# display.net
KiCad netlist of a schematic drawn in Altium Designer
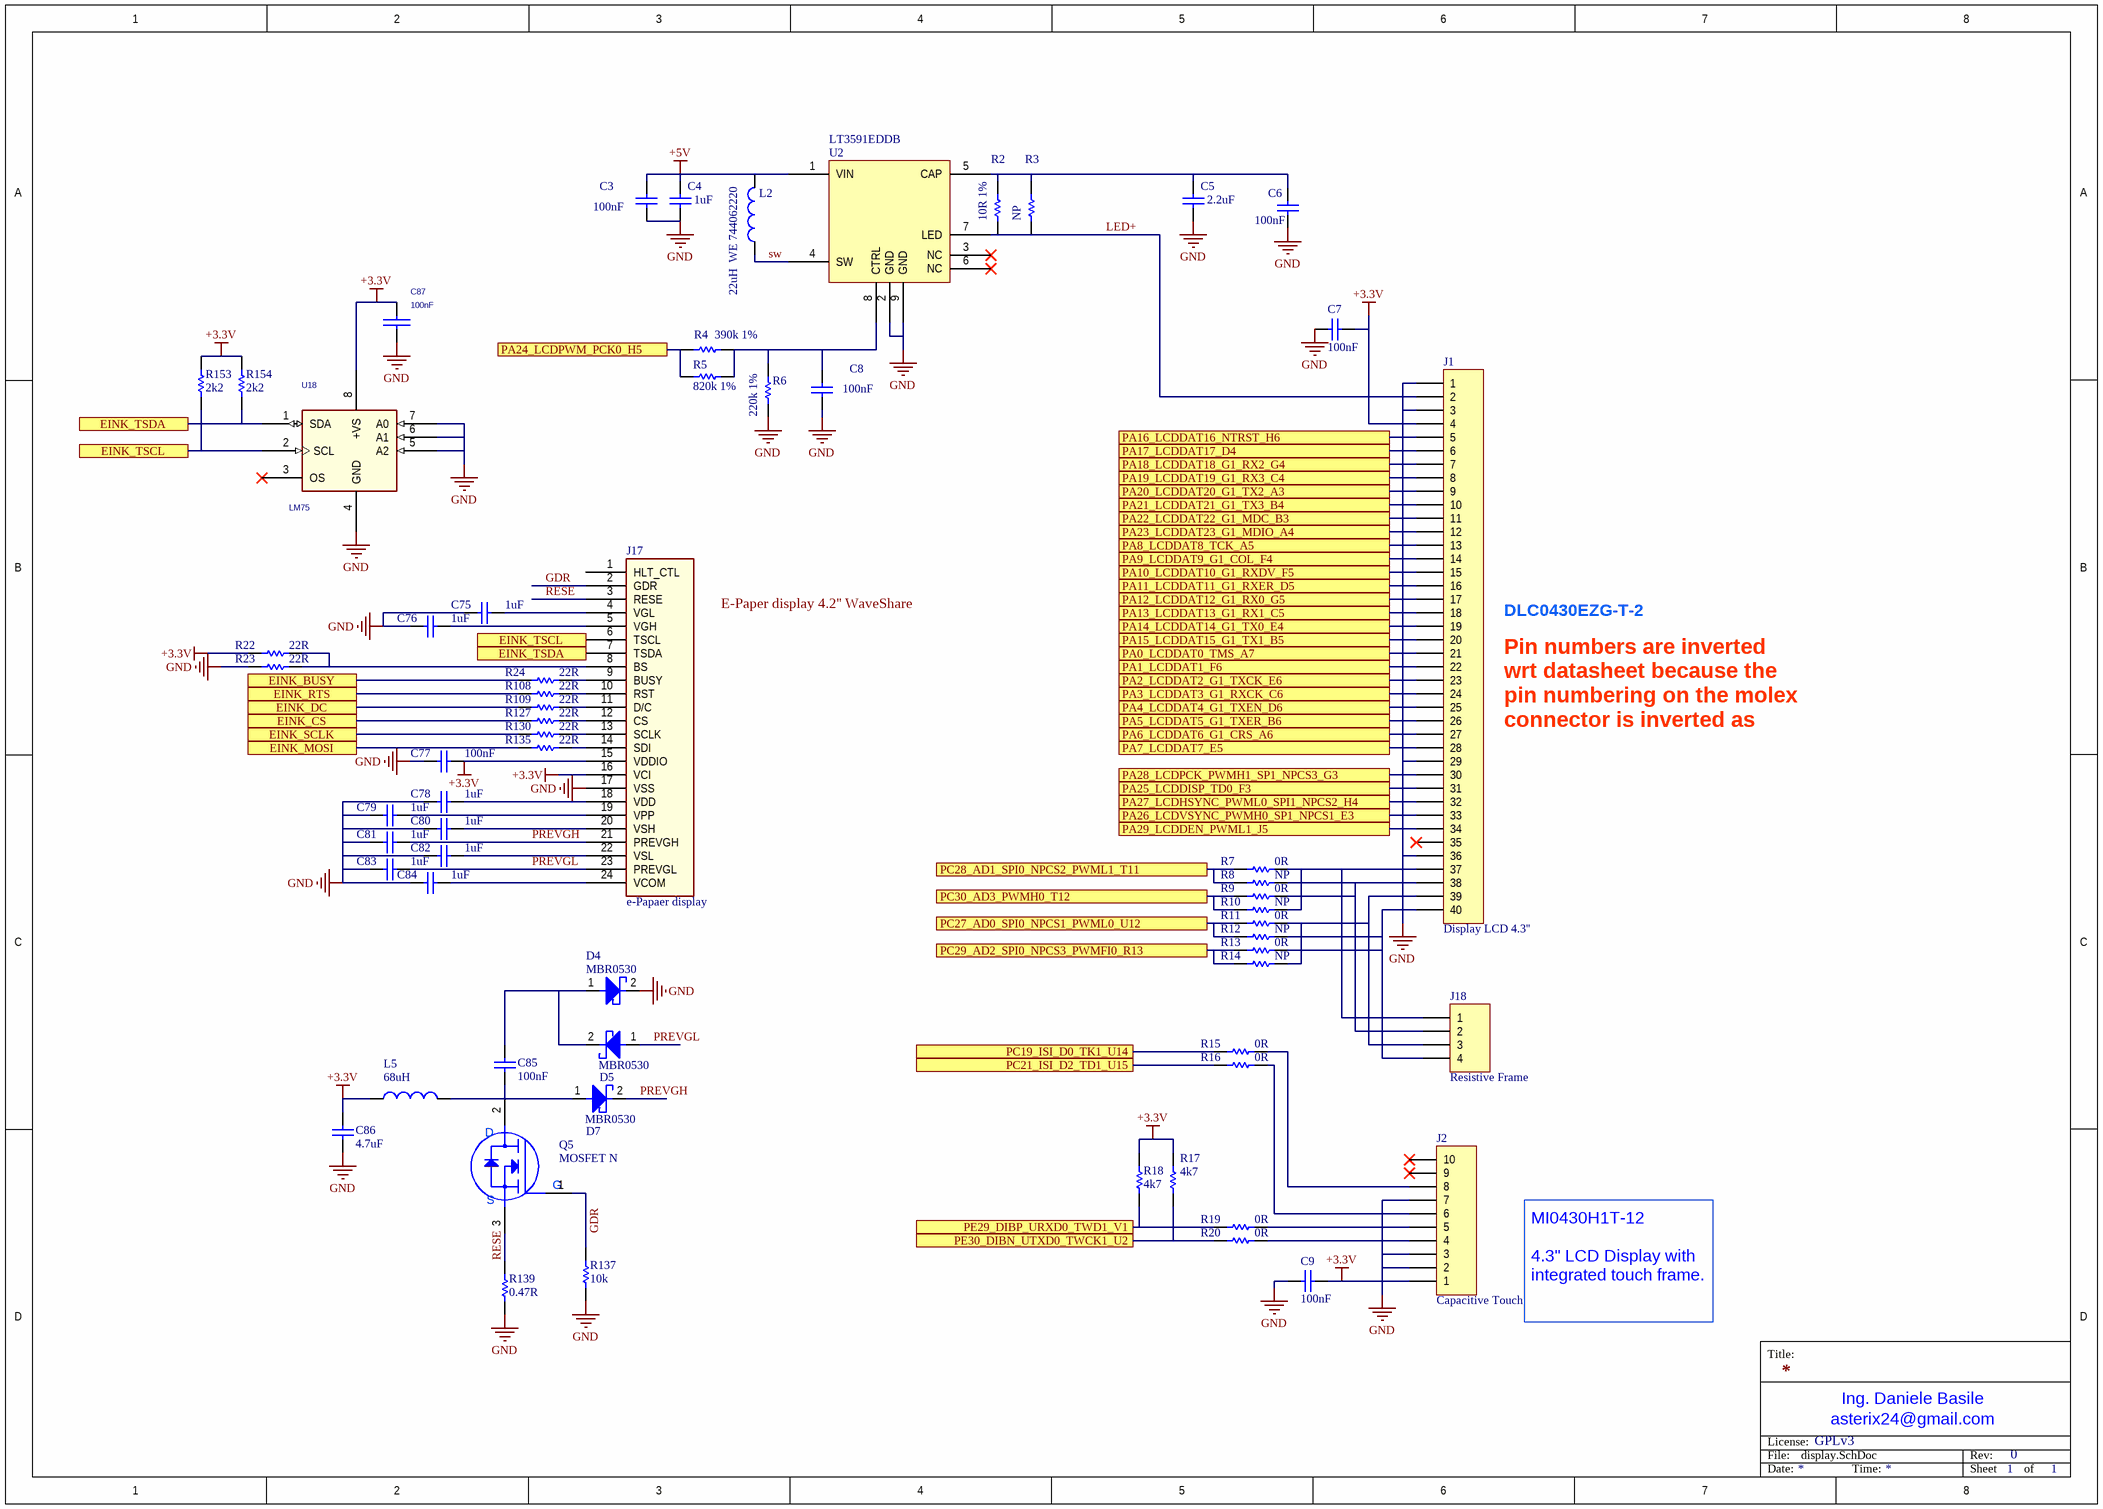
[diagram p0: display.SchDoc]

(export (version "E")
  (design (tool "Eeschema 10.0.6"))
  (components
    (comp (ref "C3")
      (value "100nF")
      (footprint "0603_[1608]")
      (description "Ceramic X7R 50V")
      (fields (field (name "PUBLISHER") "Altium Limited"))
      (libsource (lib "project42_lib") (part "Cap"))
    )
    (comp (ref "C4")
      (value "1uF")
      (footprint "0805_[2012]")
      (description "Ceramic X7R 50V")
      (fields (field (name "PUBLISHER") "Altium Limited"))
      (libsource (lib "project42_lib") (part "Cap"))
    )
    (comp (ref "C5")
      (value "2.2uF")
      (footprint "1210_[3225]")
      (description "Ceramic X7R, X5R 50V")
      (fields (field (name "PUBLISHER") "Altium Limited"))
      (libsource (lib "project42_lib") (part "Cap"))
    )
    (comp (ref "C6")
      (value "100nF")
      (footprint "0603_[1608]")
      (description "Ceramic X7R 50V")
      (fields (field (name "PUBLISHER") "Altium Limited"))
      (libsource (lib "project42_lib") (part "Cap"))
    )
    (comp (ref "C7")
      (value "100nF")
      (footprint "0603_[1608]")
      (description "Ceramic X7R 50V")
      (fields (field (name "PUBLISHER") "Altium Limited"))
      (libsource (lib "project42_lib") (part "Cap"))
    )
    (comp (ref "C8")
      (value "100nF")
      (footprint "0603_[1608]")
      (description "Ceramic X7R 50V")
      (fields (field (name "PUBLISHER") "Altium Limited"))
      (libsource (lib "project42_lib") (part "Cap"))
    )
    (comp (ref "C9")
      (value "100nF")
      (footprint "0603_[1608]")
      (description "Ceramic X7R 50V")
      (fields (field (name "PUBLISHER") "Altium Limited"))
      (libsource (lib "DEVELER_Library") (part "Cap"))
    )
    (comp (ref "C75")
      (value "1uF")
      (footprint "0603_[1608]")
      (description "Ceramic X7R 50V")
      (fields (field (name "PUBLISHER") "Altium Limited"))
      (libsource (lib "DEVELER_Library") (part "Cap"))
    )
    (comp (ref "C76")
      (value "1uF")
      (footprint "0603_[1608]")
      (description "Ceramic X7R 50V")
      (fields (field (name "PUBLISHER") "Altium Limited"))
      (libsource (lib "DEVELER_Library") (part "Cap"))
    )
    (comp (ref "C77")
      (value "100nF")
      (footprint "0603_[1608]")
      (description "Ceramic X7R 50V")
      (fields (field (name "PUBLISHER") "Altium Limited"))
      (libsource (lib "DEVELER_Library") (part "Cap"))
    )
    (comp (ref "C78")
      (value "1uF")
      (footprint "0603_[1608]")
      (description "Ceramic X7R 50V")
      (fields (field (name "PUBLISHER") "Altium Limited"))
      (libsource (lib "DEVELER_Library") (part "Cap"))
    )
    (comp (ref "C79")
      (value "1uF")
      (footprint "0603_[1608]")
      (description "Ceramic X7R 50V")
      (fields (field (name "PUBLISHER") "Altium Limited"))
      (libsource (lib "DEVELER_Library") (part "Cap"))
    )
    (comp (ref "C80")
      (value "1uF")
      (footprint "0603_[1608]")
      (description "Ceramic X7R 50V")
      (fields (field (name "PUBLISHER") "Altium Limited"))
      (libsource (lib "DEVELER_Library") (part "Cap"))
    )
    (comp (ref "C81")
      (value "1uF")
      (footprint "0603_[1608]")
      (description "Ceramic X7R 50V")
      (fields (field (name "PUBLISHER") "Altium Limited"))
      (libsource (lib "DEVELER_Library") (part "Cap"))
    )
    (comp (ref "C82")
      (value "1uF")
      (footprint "0603_[1608]")
      (description "Ceramic X7R 50V")
      (fields (field (name "PUBLISHER") "Altium Limited"))
      (libsource (lib "DEVELER_Library") (part "Cap"))
    )
    (comp (ref "C83")
      (value "1uF")
      (footprint "0603_[1608]")
      (description "Ceramic X7R 50V")
      (fields (field (name "PUBLISHER") "Altium Limited"))
      (libsource (lib "DEVELER_Library") (part "Cap"))
    )
    (comp (ref "C84")
      (value "1uF")
      (footprint "0603_[1608]")
      (description "Ceramic X7R 50V")
      (fields (field (name "PUBLISHER") "Altium Limited"))
      (libsource (lib "DEVELER_Library") (part "Cap"))
    )
    (comp (ref "C85")
      (value "100nF")
      (footprint "0603_[1608]")
      (description "Ceramic X7R 50V")
      (fields (field (name "PUBLISHER") "Altium Limited"))
      (libsource (lib "DEVELER_Library") (part "Cap"))
    )
    (comp (ref "C86")
      (value "4.7uF")
      (footprint "0603_[1608]")
      (description "Ceramic X7R 50V")
      (fields (field (name "PUBLISHER") "Altium Limited"))
      (libsource (lib "DEVELER_Library") (part "Cap"))
    )
    (comp (ref "C87")
      (value "100nF")
      (footprint "0603_[1608]")
      (description "Ceramic X7R 50V")
      (libsource (lib "fues_Library") (part "C"))
    )
    (comp (ref "D4")
      (value "MBR0530")
      (footprint "SOD-123_K2-A1")
      (description "Schottky Diodes")
      (libsource (lib "develer_library") (part "Diode_SCHOTTKY"))
    )
    (comp (ref "D5")
      (value "MBR0530")
      (footprint "SOD-123_K2-A1")
      (description "Schottky Diodes")
      (libsource (lib "develer_library") (part "Diode_SCHOTTKY"))
    )
    (comp (ref "D7")
      (value "MBR0530")
      (footprint "SOD-123_K2-A1")
      (description "Schottky Diodes")
      (libsource (lib "develer_library") (part "Diode_SCHOTTKY"))
    )
    (comp (ref "J1")
      (value "Display LCD 4.3''")
      (footprint "fcc-zif_40pin_0.5mm")
      (description "40-pin, 0.5mm, SMT, ZIF, Horizontal, Top Contact (WE 68714014022; Molex: 54104-4031)")
      (fields (field (name "PUBLISHER") "Altium Limited"))
      (libsource (lib "DEVELER_Library") (part "Header 40"))
    )
    (comp (ref "J2")
      (value "Capacitive Touch")
      (footprint "fcc-zif_10pin_0.5mm")
      (description "10-pin, 0.5mm, SMT, ZIF, Horizontal, Top Contact")
      (fields (field (name "PUBLISHER") "Altium Limited"))
      (libsource (lib "Miscellaneous Connectors") (part "Header 10"))
    )
    (comp (ref "J17")
      (value "e-Papaer display")
      (footprint "fcc-zif_24pin_0.5mm")
      (description "e-paper display wave share")
      (libsource (lib "develer_library") (part "e-paper_display_waveshare"))
    )
    (comp (ref "J18")
      (value "Resistive Frame")
      (footprint "fcc-zif_4pin_1mm")
      (description "Zip FCC connector")
      (fields (field (name "PUBLISHER") "Altium Limited"))
      (libsource (lib "Miscellaneous Connectors") (part "Header 4"))
    )
    (comp (ref "L2")
      (value "22uH  WE 744062220")
      (footprint "WE-TPC-6823-X")
      (description "Power Inductor")
      (libsource (lib "DEVELER_Library") (part "Inductor"))
    )
    (comp (ref "L5")
      (value "68uH")
      (footprint "WE-TPC-6823-X")
      (description "Power Inductor")
      (libsource (lib "DEVELER_Library") (part "Inductor"))
    )
    (comp (ref "Q5")
      (value "MOSFET N")
      (footprint "sot-23")
      (description "MOSFET Channl N")
      (libsource (lib "develer_library") (part "MOSFET-N 3pin"))
    )
    (comp (ref "R2")
      (value "10R 1%")
      (footprint "0603_[1608]")
      (description "Resistor 0.125W")
      (fields (field (name "PUBLISHER") "Altium Limited"))
      (libsource (lib "project42_lib") (part "Res1"))
    )
    (comp (ref "R3")
      (value "NP")
      (footprint "0603_[1608]")
      (description "Resistor")
      (fields (field (name "PUBLISHER") "Altium Limited"))
      (libsource (lib "project42_lib") (part "Res1"))
    )
    (comp (ref "R4")
      (value "390k 1%")
      (footprint "0603_[1608]")
      (description "Resistor")
      (fields (field (name "PUBLISHER") "Altium Limited"))
      (libsource (lib "project42_lib") (part "Res1"))
    )
    (comp (ref "R5")
      (value "820k 1%")
      (footprint "0603_[1608]")
      (description "Resistor")
      (fields (field (name "PUBLISHER") "Altium Limited"))
      (libsource (lib "project42_lib") (part "Res1"))
    )
    (comp (ref "R6")
      (value "220k 1%")
      (footprint "0603_[1608]")
      (description "Resistor")
      (fields (field (name "PUBLISHER") "Altium Limited"))
      (libsource (lib "project42_lib") (part "Res1"))
    )
    (comp (ref "R7")
      (value "0R")
      (footprint "0603_[1608]")
      (description "Resistor")
      (fields (field (name "PUBLISHER") "Altium Limited"))
      (libsource (lib "project42_lib") (part "Res1"))
    )
    (comp (ref "R8")
      (value "NP")
      (footprint "0603_[1608]")
      (description "Resistor")
      (fields (field (name "PUBLISHER") "Altium Limited"))
      (libsource (lib "project42_lib") (part "Res1"))
    )
    (comp (ref "R9")
      (value "0R")
      (footprint "0603_[1608]")
      (description "Resistor")
      (fields (field (name "PUBLISHER") "Altium Limited"))
      (libsource (lib "project42_lib") (part "Res1"))
    )
    (comp (ref "R10")
      (value "NP")
      (footprint "0603_[1608]")
      (description "Resistor")
      (fields (field (name "PUBLISHER") "Altium Limited"))
      (libsource (lib "project42_lib") (part "Res1"))
    )
    (comp (ref "R11")
      (value "0R")
      (footprint "0603_[1608]")
      (description "Resistor")
      (fields (field (name "PUBLISHER") "Altium Limited"))
      (libsource (lib "project42_lib") (part "Res1"))
    )
    (comp (ref "R12")
      (value "NP")
      (footprint "0603_[1608]")
      (description "Resistor")
      (fields (field (name "PUBLISHER") "Altium Limited"))
      (libsource (lib "project42_lib") (part "Res1"))
    )
    (comp (ref "R13")
      (value "0R")
      (footprint "0603_[1608]")
      (description "Resistor")
      (fields (field (name "PUBLISHER") "Altium Limited"))
      (libsource (lib "project42_lib") (part "Res1"))
    )
    (comp (ref "R14")
      (value "NP")
      (footprint "0603_[1608]")
      (description "Resistor")
      (fields (field (name "PUBLISHER") "Altium Limited"))
      (libsource (lib "project42_lib") (part "Res1"))
    )
    (comp (ref "R15")
      (value "0R")
      (footprint "0603_[1608]")
      (description "Resistor")
      (fields (field (name "PUBLISHER") "Altium Limited"))
      (libsource (lib "DEVELER_Library") (part "Res1"))
    )
    (comp (ref "R16")
      (value "0R")
      (footprint "0603_[1608]")
      (description "Resistor")
      (fields (field (name "PUBLISHER") "Altium Limited"))
      (libsource (lib "DEVELER_Library") (part "Res1"))
    )
    (comp (ref "R17")
      (value "4k7")
      (footprint "0603_[1608]")
      (description "Resistor")
      (fields (field (name "PUBLISHER") "Altium Limited"))
      (libsource (lib "DEVELER_Library") (part "Res1"))
    )
    (comp (ref "R18")
      (value "4k7")
      (footprint "0603_[1608]")
      (description "Resistor")
      (fields (field (name "PUBLISHER") "Altium Limited"))
      (libsource (lib "DEVELER_Library") (part "Res1"))
    )
    (comp (ref "R19")
      (value "0R")
      (footprint "0603_[1608]")
      (description "Resistor")
      (fields (field (name "PUBLISHER") "Altium Limited"))
      (libsource (lib "DEVELER_Library") (part "Res1"))
    )
    (comp (ref "R20")
      (value "0R")
      (footprint "0603_[1608]")
      (description "Resistor")
      (fields (field (name "PUBLISHER") "Altium Limited"))
      (libsource (lib "DEVELER_Library") (part "Res1"))
    )
    (comp (ref "R22")
      (value "22R")
      (footprint "0603_[1608]")
      (description "Resistor")
      (fields (field (name "PUBLISHER") "Altium Limited"))
      (libsource (lib "project42_lib") (part "Res1"))
    )
    (comp (ref "R23")
      (value "22R")
      (footprint "0603_[1608]")
      (description "Resistor")
      (fields (field (name "PUBLISHER") "Altium Limited"))
      (libsource (lib "project42_lib") (part "Res1"))
    )
    (comp (ref "R24")
      (value "22R")
      (footprint "0603_[1608]")
      (description "Resistor")
      (fields (field (name "PUBLISHER") "Altium Limited"))
      (libsource (lib "project42_lib") (part "Res1"))
    )
    (comp (ref "R108")
      (value "22R")
      (footprint "0603_[1608]")
      (description "Resistor")
      (fields (field (name "PUBLISHER") "Altium Limited"))
      (libsource (lib "project42_lib") (part "Res1"))
    )
    (comp (ref "R109")
      (value "22R")
      (footprint "0603_[1608]")
      (description "Resistor")
      (fields (field (name "PUBLISHER") "Altium Limited"))
      (libsource (lib "project42_lib") (part "Res1"))
    )
    (comp (ref "R127")
      (value "22R")
      (footprint "0603_[1608]")
      (description "Resistor")
      (fields (field (name "PUBLISHER") "Altium Limited"))
      (libsource (lib "project42_lib") (part "Res1"))
    )
    (comp (ref "R130")
      (value "22R")
      (footprint "0603_[1608]")
      (description "Resistor")
      (fields (field (name "PUBLISHER") "Altium Limited"))
      (libsource (lib "project42_lib") (part "Res1"))
    )
    (comp (ref "R135")
      (value "22R")
      (footprint "0603_[1608]")
      (description "Resistor")
      (fields (field (name "PUBLISHER") "Altium Limited"))
      (libsource (lib "project42_lib") (part "Res1"))
    )
    (comp (ref "R137")
      (value "10k")
      (footprint "0603_[1608]")
      (description "Resistor")
      (fields (field (name "PUBLISHER") "Altium Limited"))
      (libsource (lib "project42_lib") (part "Res1"))
    )
    (comp (ref "R139")
      (value "0.47R")
      (footprint "0603_[1608]")
      (description "Resistor")
      (fields (field (name "PUBLISHER") "Altium Limited"))
      (libsource (lib "project42_lib") (part "Res1"))
    )
    (comp (ref "R153")
      (value "2k2")
      (footprint "0603_[1608]")
      (description "Resistor")
      (fields (field (name "PUBLISHER") "Altium Limited"))
      (libsource (lib "project42_lib") (part "Res1"))
    )
    (comp (ref "R154")
      (value "2k2")
      (footprint "0603_[1608]")
      (description "Resistor")
      (fields (field (name "PUBLISHER") "Altium Limited"))
      (libsource (lib "project42_lib") (part "Res1"))
    )
    (comp (ref "U2")
      (value "LT3591EDDB")
      (footprint "PQFN50P300X200X75_HS-9L")
      (description "White LED Driver with Integrated Schottky")
      (libsource (lib "DEVELER_Library") (part "LT3591"))
    )
    (comp (ref "U18")
      (value "LM75")
      (footprint "SOIC8")
      (description "IC LM75BIM-3.0")
      (libsource (lib "fues_Library") (part "LM75"))
    )
  )
  (nets
    (net (code "1") (name "+3.3V") (class "Default")
      (node (ref "C7") (pin "1") (pinfunction "1_1") (pintype "passive"))
      (node (ref "C77") (pin "1") (pinfunction "1_1") (pintype "passive"))
      (node (ref "C86") (pin "1") (pinfunction "1_1") (pintype "passive"))
      (node (ref "C87") (pin "1") (pinfunction "1_1") (pintype "passive"))
      (node (ref "C9") (pin "1") (pinfunction "1_1") (pintype "passive"))
      (node (ref "J1") (pin "4") (pinfunction "4_4") (pintype "passive"))
      (node (ref "J17") (pin "15") (pinfunction "VDDIO_15") (pintype "passive"))
      (node (ref "J17") (pin "16") (pinfunction "VCI_16") (pintype "passive"))
      (node (ref "J2") (pin "1") (pinfunction "1_1") (pintype "passive"))
      (node (ref "L5") (pin "1") (pinfunction "1_1") (pintype "passive"))
      (node (ref "R153") (pin "1") (pinfunction "1_1") (pintype "passive"))
      (node (ref "R154") (pin "1") (pinfunction "1_1") (pintype "passive"))
      (node (ref "R17") (pin "1") (pinfunction "1_1") (pintype "passive"))
      (node (ref "R18") (pin "1") (pinfunction "1_1") (pintype "passive"))
      (node (ref "R22") (pin "2") (pinfunction "2_2") (pintype "passive"))
      (node (ref "U18") (pin "8") (pinfunction "+VS_8") (pintype "power_in"))
    )
    (net (code "2") (name "+5V") (class "Default")
      (node (ref "C3") (pin "2") (pinfunction "2_2") (pintype "passive"))
      (node (ref "C4") (pin "2") (pinfunction "2_2") (pintype "passive"))
      (node (ref "L2") (pin "2") (pinfunction "2_2") (pintype "passive"))
      (node (ref "U2") (pin "1") (pinfunction "VIN_1") (pintype "power_in"))
    )
    (net (code "3") (name "/EINK_BUSY") (class "Default")
      (node (ref "R24") (pin "2") (pinfunction "2_2") (pintype "passive"))
    )
    (net (code "4") (name "/EINK_CS") (class "Default")
      (node (ref "R127") (pin "2") (pinfunction "2_2") (pintype "passive"))
    )
    (net (code "5") (name "/EINK_DC") (class "Default")
      (node (ref "R109") (pin "2") (pinfunction "2_2") (pintype "passive"))
    )
    (net (code "6") (name "/EINK_MOSI") (class "Default")
      (node (ref "R135") (pin "2") (pinfunction "2_2") (pintype "passive"))
    )
    (net (code "7") (name "/EINK_RTS") (class "Default")
      (node (ref "R108") (pin "2") (pinfunction "2_2") (pintype "passive"))
    )
    (net (code "8") (name "/EINK_SCLK") (class "Default")
      (node (ref "R130") (pin "2") (pinfunction "2_2") (pintype "passive"))
    )
    (net (code "9") (name "/EINK_TSCL") (class "Default")
      (node (ref "J17") (pin "6") (pinfunction "TSCL_6") (pintype "passive"))
      (node (ref "R153") (pin "2") (pinfunction "2_2") (pintype "passive"))
      (node (ref "U18") (pin "2") (pinfunction "SCL_2") (pintype "input"))
    )
    (net (code "10") (name "/EINK_TSDA") (class "Default")
      (node (ref "J17") (pin "7") (pinfunction "TSDA_7") (pintype "passive"))
      (node (ref "R154") (pin "2") (pinfunction "2_2") (pintype "passive"))
      (node (ref "U18") (pin "1") (pinfunction "SDA_1") (pintype "bidirectional"))
    )
    (net (code "11") (name "/GDR") (class "Default")
      (node (ref "J17") (pin "2") (pinfunction "GDR_2") (pintype "passive"))
      (node (ref "Q5") (pin "1") (pinfunction "G_1") (pintype "passive"))
      (node (ref "R137") (pin "1") (pinfunction "1_1") (pintype "passive"))
    )
    (net (code "12") (name "/LED+") (class "Default")
      (node (ref "J1") (pin "2") (pinfunction "2_2") (pintype "passive"))
      (node (ref "R2") (pin "1") (pinfunction "1_1") (pintype "passive"))
      (node (ref "R3") (pin "1") (pinfunction "1_1") (pintype "passive"))
      (node (ref "U2") (pin "7") (pinfunction "LED_7") (pintype "passive"))
    )
    (net (code "13") (name "/PA0_LCDDAT0_TMS_A7") (class "Default")
      (node (ref "J1") (pin "21") (pinfunction "21_21") (pintype "passive"))
    )
    (net (code "14") (name "/PA1_LCDDAT1_F6") (class "Default")
      (node (ref "J1") (pin "22") (pinfunction "22_22") (pintype "passive"))
    )
    (net (code "15") (name "/PA2_LCDDAT2_G1_TXCK_E6") (class "Default")
      (node (ref "J1") (pin "23") (pinfunction "23_23") (pintype "passive"))
    )
    (net (code "16") (name "/PA3_LCDDAT3_G1_RXCK_C6") (class "Default")
      (node (ref "J1") (pin "24") (pinfunction "24_24") (pintype "passive"))
    )
    (net (code "17") (name "/PA4_LCDDAT4_G1_TXEN_D6") (class "Default")
      (node (ref "J1") (pin "25") (pinfunction "25_25") (pintype "passive"))
    )
    (net (code "18") (name "/PA5_LCDDAT5_G1_TXER_B6") (class "Default")
      (node (ref "J1") (pin "26") (pinfunction "26_26") (pintype "passive"))
    )
    (net (code "19") (name "/PA6_LCDDAT6_G1_CRS_A6") (class "Default")
      (node (ref "J1") (pin "27") (pinfunction "27_27") (pintype "passive"))
    )
    (net (code "20") (name "/PA7_LCDDAT7_E5") (class "Default")
      (node (ref "J1") (pin "28") (pinfunction "28_28") (pintype "passive"))
    )
    (net (code "21") (name "/PA8_LCDDAT8_TCK_A5") (class "Default")
      (node (ref "J1") (pin "13") (pinfunction "13_13") (pintype "passive"))
    )
    (net (code "22") (name "/PA9_LCDDAT9_G1_COL_F4") (class "Default")
      (node (ref "J1") (pin "14") (pinfunction "14_14") (pintype "passive"))
    )
    (net (code "23") (name "/PA10_LCDDAT10_G1_RXDV_F5") (class "Default")
      (node (ref "J1") (pin "15") (pinfunction "15_15") (pintype "passive"))
    )
    (net (code "24") (name "/PA11_LCDDAT11_G1_RXER_D5") (class "Default")
      (node (ref "J1") (pin "16") (pinfunction "16_16") (pintype "passive"))
    )
    (net (code "25") (name "/PA12_LCDDAT12_G1_RX0_G5") (class "Default")
      (node (ref "J1") (pin "17") (pinfunction "17_17") (pintype "passive"))
    )
    (net (code "26") (name "/PA13_LCDDAT13_G1_RX1_C5") (class "Default")
      (node (ref "J1") (pin "18") (pinfunction "18_18") (pintype "passive"))
    )
    (net (code "27") (name "/PA14_LCDDAT14_G1_TX0_E4") (class "Default")
      (node (ref "J1") (pin "19") (pinfunction "19_19") (pintype "passive"))
    )
    (net (code "28") (name "/PA15_LCDDAT15_G1_TX1_B5") (class "Default")
      (node (ref "J1") (pin "20") (pinfunction "20_20") (pintype "passive"))
    )
    (net (code "29") (name "/PA16_LCDDAT16_NTRST_H6") (class "Default")
      (node (ref "J1") (pin "5") (pinfunction "5_5") (pintype "passive"))
    )
    (net (code "30") (name "/PA17_LCDDAT17_D4") (class "Default")
      (node (ref "J1") (pin "6") (pinfunction "6_6") (pintype "passive"))
    )
    (net (code "31") (name "/PA18_LCDDAT18_G1_RX2_G4") (class "Default")
      (node (ref "J1") (pin "7") (pinfunction "7_7") (pintype "passive"))
    )
    (net (code "32") (name "/PA19_LCDDAT19_G1_RX3_C4") (class "Default")
      (node (ref "J1") (pin "8") (pinfunction "8_8") (pintype "passive"))
    )
    (net (code "33") (name "/PA20_LCDDAT20_G1_TX2_A3") (class "Default")
      (node (ref "J1") (pin "9") (pinfunction "9_9") (pintype "passive"))
    )
    (net (code "34") (name "/PA21_LCDDAT21_G1_TX3_B4") (class "Default")
      (node (ref "J1") (pin "10") (pinfunction "10_10") (pintype "passive"))
    )
    (net (code "35") (name "/PA22_LCDDAT22_G1_MDC_B3") (class "Default")
      (node (ref "J1") (pin "11") (pinfunction "11_11") (pintype "passive"))
    )
    (net (code "36") (name "/PA23_LCDDAT23_G1_MDIO_A4") (class "Default")
      (node (ref "J1") (pin "12") (pinfunction "12_12") (pintype "passive"))
    )
    (net (code "37") (name "/PA24_LCDPWM_PCK0_H5") (class "Default")
      (node (ref "R4") (pin "2") (pinfunction "2_2") (pintype "passive"))
      (node (ref "R5") (pin "1") (pinfunction "1_1") (pintype "passive"))
    )
    (net (code "38") (name "/PA25_LCDDISP_TD0_F3") (class "Default")
      (node (ref "J1") (pin "31") (pinfunction "31_31") (pintype "passive"))
    )
    (net (code "39") (name "/PA26_LCDVSYNC_PWMH0_SP1_NPCS1_E3") (class "Default")
      (node (ref "J1") (pin "33") (pinfunction "33_33") (pintype "passive"))
    )
    (net (code "40") (name "/PA27_LCDHSYNC_PWML0_SPI1_NPCS2_H4") (class "Default")
      (node (ref "J1") (pin "32") (pinfunction "32_32") (pintype "passive"))
    )
    (net (code "41") (name "/PA28_LCDPCK_PWMH1_SP1_NPCS3_G3") (class "Default")
      (node (ref "J1") (pin "30") (pinfunction "30_30") (pintype "passive"))
    )
    (net (code "42") (name "/PA29_LCDDEN_PWML1_J5") (class "Default")
      (node (ref "J1") (pin "34") (pinfunction "34_34") (pintype "passive"))
    )
    (net (code "43") (name "/PC19_ISI_D0_TK1_U14") (class "Default")
      (node (ref "R15") (pin "2") (pinfunction "2_2") (pintype "passive"))
    )
    (net (code "44") (name "/PC21_ISI_D2_TD1_U15") (class "Default")
      (node (ref "R16") (pin "2") (pinfunction "2_2") (pintype "passive"))
    )
    (net (code "45") (name "/PC27_AD0_SPI0_NPCS1_PWML0_U12") (class "Default")
      (node (ref "R11") (pin "2") (pinfunction "2_2") (pintype "passive"))
      (node (ref "R12") (pin "2") (pinfunction "2_2") (pintype "passive"))
    )
    (net (code "46") (name "/PC28_AD1_SPI0_NPCS2_PWML1_T11") (class "Default")
      (node (ref "R7") (pin "2") (pinfunction "2_2") (pintype "passive"))
      (node (ref "R8") (pin "2") (pinfunction "2_2") (pintype "passive"))
    )
    (net (code "47") (name "/PC29_AD2_SPI0_NPCS3_PWMFI0_R13") (class "Default")
      (node (ref "R13") (pin "2") (pinfunction "2_2") (pintype "passive"))
      (node (ref "R14") (pin "2") (pinfunction "2_2") (pintype "passive"))
    )
    (net (code "48") (name "/PC30_AD3_PWMH0_T12") (class "Default")
      (node (ref "R10") (pin "2") (pinfunction "2_2") (pintype "passive"))
      (node (ref "R9") (pin "2") (pinfunction "2_2") (pintype "passive"))
    )
    (net (code "49") (name "/PE29_DIBP_URXD0_TWD1_V1") (class "Default")
      (node (ref "R18") (pin "2") (pinfunction "2_2") (pintype "passive"))
      (node (ref "R19") (pin "2") (pinfunction "2_2") (pintype "passive"))
    )
    (net (code "50") (name "/PE30_DIBN_UTXD0_TWCK1_U2") (class "Default")
      (node (ref "R17") (pin "2") (pinfunction "2_2") (pintype "passive"))
      (node (ref "R20") (pin "2") (pinfunction "2_2") (pintype "passive"))
    )
    (net (code "51") (name "/PREVGH") (class "Default")
      (node (ref "C81") (pin "1") (pinfunction "1_1") (pintype "passive"))
      (node (ref "D7") (pin "2") (pinfunction "K_2") (pintype "passive"))
      (node (ref "J17") (pin "21") (pinfunction "PREVGH_21") (pintype "passive"))
    )
    (net (code "52") (name "/PREVGL") (class "Default")
      (node (ref "C83") (pin "1") (pinfunction "1_1") (pintype "passive"))
      (node (ref "D5") (pin "1") (pinfunction "A_1") (pintype "passive"))
      (node (ref "J17") (pin "23") (pinfunction "PREVGL_23") (pintype "passive"))
    )
    (net (code "53") (name "/RESE") (class "Default")
      (node (ref "J17") (pin "3") (pinfunction "RESE_3") (pintype "passive"))
      (node (ref "Q5") (pin "3") (pinfunction "S_3") (pintype "passive"))
      (node (ref "R139") (pin "1") (pinfunction "1_1") (pintype "passive"))
    )
    (net (code "54") (name "/sw") (class "Default")
      (node (ref "L2") (pin "1") (pinfunction "1_1") (pintype "passive"))
      (node (ref "U2") (pin "4") (pinfunction "SW_4") (pintype "passive"))
    )
    (net (code "55") (name "GND") (class "Default")
      (node (ref "C3") (pin "1") (pinfunction "1_1") (pintype "passive"))
      (node (ref "C4") (pin "1") (pinfunction "1_1") (pintype "passive"))
      (node (ref "C5") (pin "1") (pinfunction "1_1") (pintype "passive"))
      (node (ref "C6") (pin "1") (pinfunction "1_1") (pintype "passive"))
      (node (ref "C7") (pin "2") (pinfunction "2_2") (pintype "passive"))
      (node (ref "C75") (pin "2") (pinfunction "2_2") (pintype "passive"))
      (node (ref "C76") (pin "2") (pinfunction "2_2") (pintype "passive"))
      (node (ref "C77") (pin "2") (pinfunction "2_2") (pintype "passive"))
      (node (ref "C78") (pin "2") (pinfunction "2_2") (pintype "passive"))
      (node (ref "C79") (pin "2") (pinfunction "2_2") (pintype "passive"))
      (node (ref "C8") (pin "1") (pinfunction "1_1") (pintype "passive"))
      (node (ref "C80") (pin "2") (pinfunction "2_2") (pintype "passive"))
      (node (ref "C81") (pin "2") (pinfunction "2_2") (pintype "passive"))
      (node (ref "C82") (pin "2") (pinfunction "2_2") (pintype "passive"))
      (node (ref "C83") (pin "2") (pinfunction "2_2") (pintype "passive"))
      (node (ref "C84") (pin "2") (pinfunction "2_2") (pintype "passive"))
      (node (ref "C86") (pin "2") (pinfunction "2_2") (pintype "passive"))
      (node (ref "C87") (pin "2") (pinfunction "2_2") (pintype "passive"))
      (node (ref "C9") (pin "2") (pinfunction "2_2") (pintype "passive"))
      (node (ref "D4") (pin "2") (pinfunction "K_2") (pintype "passive"))
      (node (ref "J1") (pin "1") (pinfunction "1_1") (pintype "passive"))
      (node (ref "J1") (pin "29") (pinfunction "29_29") (pintype "passive"))
      (node (ref "J1") (pin "3") (pinfunction "3_3") (pintype "passive"))
      (node (ref "J1") (pin "36") (pinfunction "36_36") (pintype "passive"))
      (node (ref "J17") (pin "17") (pinfunction "VSS_17") (pintype "passive"))
      (node (ref "J2") (pin "2") (pinfunction "2_2") (pintype "passive"))
      (node (ref "J2") (pin "3") (pinfunction "3_3") (pintype "passive"))
      (node (ref "J2") (pin "7") (pinfunction "7_7") (pintype "passive"))
      (node (ref "R137") (pin "2") (pinfunction "2_2") (pintype "passive"))
      (node (ref "R139") (pin "2") (pinfunction "2_2") (pintype "passive"))
      (node (ref "R23") (pin "2") (pinfunction "2_2") (pintype "passive"))
      (node (ref "R6") (pin "2") (pinfunction "2_2") (pintype "passive"))
      (node (ref "U18") (pin "4") (pinfunction "GND_4") (pintype "power_in"))
      (node (ref "U18") (pin "5") (pinfunction "A2_5") (pintype "input"))
      (node (ref "U18") (pin "6") (pinfunction "A1_6") (pintype "input"))
      (node (ref "U18") (pin "7") (pinfunction "A0_7") (pintype "input"))
      (node (ref "U2") (pin "2") (pinfunction "GND_2") (pintype "power_in"))
      (node (ref "U2") (pin "9") (pinfunction "GND_9") (pintype "power_in"))
    )
    (net (code "56") (name "Net-(D4-A)") (class "Default")
      (node (ref "C85") (pin "1") (pinfunction "1_1") (pintype "passive"))
      (node (ref "D4") (pin "1") (pinfunction "A_1") (pintype "passive"))
      (node (ref "D5") (pin "2") (pinfunction "K_2") (pintype "passive"))
    )
    (net (code "57") (name "Net-(D7-A)") (class "Default")
      (node (ref "C85") (pin "2") (pinfunction "2_2") (pintype "passive"))
      (node (ref "D7") (pin "1") (pinfunction "A_1") (pintype "passive"))
      (node (ref "L5") (pin "2") (pinfunction "2_2") (pintype "passive"))
      (node (ref "Q5") (pin "2") (pinfunction "D_2") (pintype "passive"))
    )
    (net (code "58") (name "Net-(J1-Pad37)") (class "Default")
      (node (ref "J1") (pin "37") (pinfunction "37_37") (pintype "passive"))
      (node (ref "J18") (pin "1") (pinfunction "1_1") (pintype "passive"))
      (node (ref "R10") (pin "1") (pinfunction "1_1") (pintype "passive"))
      (node (ref "R7") (pin "1") (pinfunction "1_1") (pintype "passive"))
    )
    (net (code "59") (name "Net-(J1-Pad38)") (class "Default")
      (node (ref "J1") (pin "38") (pinfunction "38_38") (pintype "passive"))
      (node (ref "J18") (pin "2") (pinfunction "2_2") (pintype "passive"))
      (node (ref "R8") (pin "1") (pinfunction "1_1") (pintype "passive"))
      (node (ref "R9") (pin "1") (pinfunction "1_1") (pintype "passive"))
    )
    (net (code "60") (name "Net-(J1-Pad39)") (class "Default")
      (node (ref "J1") (pin "39") (pinfunction "39_39") (pintype "passive"))
      (node (ref "J18") (pin "3") (pinfunction "3_3") (pintype "passive"))
      (node (ref "R11") (pin "1") (pinfunction "1_1") (pintype "passive"))
      (node (ref "R14") (pin "1") (pinfunction "1_1") (pintype "passive"))
    )
    (net (code "61") (name "Net-(J1-Pad40)") (class "Default")
      (node (ref "J1") (pin "40") (pinfunction "40_40") (pintype "passive"))
      (node (ref "J18") (pin "4") (pinfunction "4_4") (pintype "passive"))
      (node (ref "R12") (pin "1") (pinfunction "1_1") (pintype "passive"))
      (node (ref "R13") (pin "1") (pinfunction "1_1") (pintype "passive"))
    )
    (net (code "62") (name "Net-(J2-Pad4)") (class "Default")
      (node (ref "J2") (pin "4") (pinfunction "4_4") (pintype "passive"))
      (node (ref "R20") (pin "1") (pinfunction "1_1") (pintype "passive"))
    )
    (net (code "63") (name "Net-(J2-Pad5)") (class "Default")
      (node (ref "J2") (pin "5") (pinfunction "5_5") (pintype "passive"))
      (node (ref "R19") (pin "1") (pinfunction "1_1") (pintype "passive"))
    )
    (net (code "64") (name "Net-(J2-Pad6)") (class "Default")
      (node (ref "J2") (pin "6") (pinfunction "6_6") (pintype "passive"))
      (node (ref "R16") (pin "1") (pinfunction "1_1") (pintype "passive"))
    )
    (net (code "65") (name "Net-(J2-Pad8)") (class "Default")
      (node (ref "J2") (pin "8") (pinfunction "8_8") (pintype "passive"))
      (node (ref "R15") (pin "1") (pinfunction "1_1") (pintype "passive"))
    )
    (net (code "66") (name "Net-(J17-BS)") (class "Default")
      (node (ref "J17") (pin "8") (pinfunction "BS_8") (pintype "passive"))
      (node (ref "R22") (pin "1") (pinfunction "1_1") (pintype "passive"))
      (node (ref "R23") (pin "1") (pinfunction "1_1") (pintype "passive"))
    )
    (net (code "67") (name "Net-(J17-BUSY)") (class "Default")
      (node (ref "J17") (pin "9") (pinfunction "BUSY_9") (pintype "passive"))
      (node (ref "R24") (pin "1") (pinfunction "1_1") (pintype "passive"))
    )
    (net (code "68") (name "Net-(J17-CS)") (class "Default")
      (node (ref "J17") (pin "12") (pinfunction "CS_12") (pintype "passive"))
      (node (ref "R127") (pin "1") (pinfunction "1_1") (pintype "passive"))
    )
    (net (code "69") (name "Net-(J17-D{slash}C)") (class "Default")
      (node (ref "J17") (pin "11") (pinfunction "D/C_11") (pintype "passive"))
      (node (ref "R109") (pin "1") (pinfunction "1_1") (pintype "passive"))
    )
    (net (code "70") (name "Net-(J17-RST)") (class "Default")
      (node (ref "J17") (pin "10") (pinfunction "RST_10") (pintype "passive"))
      (node (ref "R108") (pin "1") (pinfunction "1_1") (pintype "passive"))
    )
    (net (code "71") (name "Net-(J17-SCLK)") (class "Default")
      (node (ref "J17") (pin "13") (pinfunction "SCLK_13") (pintype "passive"))
      (node (ref "R130") (pin "1") (pinfunction "1_1") (pintype "passive"))
    )
    (net (code "72") (name "Net-(J17-SDI)") (class "Default")
      (node (ref "J17") (pin "14") (pinfunction "SDI_14") (pintype "passive"))
      (node (ref "R135") (pin "1") (pinfunction "1_1") (pintype "passive"))
    )
    (net (code "73") (name "Net-(J17-VCOM)") (class "Default")
      (node (ref "C84") (pin "1") (pinfunction "1_1") (pintype "passive"))
      (node (ref "J17") (pin "24") (pinfunction "VCOM_24") (pintype "passive"))
    )
    (net (code "74") (name "Net-(J17-VDD)") (class "Default")
      (node (ref "C78") (pin "1") (pinfunction "1_1") (pintype "passive"))
      (node (ref "J17") (pin "18") (pinfunction "VDD_18") (pintype "passive"))
    )
    (net (code "75") (name "Net-(J17-VGH)") (class "Default")
      (node (ref "C76") (pin "1") (pinfunction "1_1") (pintype "passive"))
      (node (ref "J17") (pin "5") (pinfunction "VGH_5") (pintype "passive"))
    )
    (net (code "76") (name "Net-(J17-VGL)") (class "Default")
      (node (ref "C75") (pin "1") (pinfunction "1_1") (pintype "passive"))
      (node (ref "J17") (pin "4") (pinfunction "VGL_4") (pintype "passive"))
    )
    (net (code "77") (name "Net-(J17-VPP)") (class "Default")
      (node (ref "C79") (pin "1") (pinfunction "1_1") (pintype "passive"))
      (node (ref "J17") (pin "19") (pinfunction "VPP_19") (pintype "passive"))
    )
    (net (code "78") (name "Net-(J17-VSH)") (class "Default")
      (node (ref "C80") (pin "1") (pinfunction "1_1") (pintype "passive"))
      (node (ref "J17") (pin "20") (pinfunction "VSH_20") (pintype "passive"))
    )
    (net (code "79") (name "Net-(J17-VSL)") (class "Default")
      (node (ref "C82") (pin "1") (pinfunction "1_1") (pintype "passive"))
      (node (ref "J17") (pin "22") (pinfunction "VSL_22") (pintype "passive"))
    )
    (net (code "80") (name "Net-(U2-CAP)") (class "Default")
      (node (ref "C5") (pin "2") (pinfunction "2_2") (pintype "passive"))
      (node (ref "C6") (pin "2") (pinfunction "2_2") (pintype "passive"))
      (node (ref "R2") (pin "2") (pinfunction "2_2") (pintype "passive"))
      (node (ref "R3") (pin "2") (pinfunction "2_2") (pintype "passive"))
      (node (ref "U2") (pin "5") (pinfunction "CAP_5") (pintype "passive"))
    )
    (net (code "81") (name "Net-(U2-CTRL)") (class "Default")
      (node (ref "C8") (pin "2") (pinfunction "2_2") (pintype "passive"))
      (node (ref "R4") (pin "1") (pinfunction "1_1") (pintype "passive"))
      (node (ref "R5") (pin "2") (pinfunction "2_2") (pintype "passive"))
      (node (ref "R6") (pin "1") (pinfunction "1_1") (pintype "passive"))
      (node (ref "U2") (pin "8") (pinfunction "CTRL_8") (pintype "passive"))
    )
    (net (code "82") (name "unconnected-(J1-Pad35)") (class "Default")
      (node (ref "J1") (pin "35") (pinfunction "35_35") (pintype "passive+no_connect"))
    )
    (net (code "83") (name "unconnected-(J2-Pad9)") (class "Default")
      (node (ref "J2") (pin "9") (pinfunction "9_9") (pintype "passive+no_connect"))
    )
    (net (code "84") (name "unconnected-(J2-Pad10)") (class "Default")
      (node (ref "J2") (pin "10") (pinfunction "10_10") (pintype "passive+no_connect"))
    )
    (net (code "85") (name "unconnected-(J17-HLT_CTL-Pad1)") (class "Default")
      (node (ref "J17") (pin "1") (pinfunction "HLT_CTL_1") (pintype "passive"))
    )
    (net (code "86") (name "unconnected-(U2-NC-Pad3)") (class "Default")
      (node (ref "U2") (pin "3") (pinfunction "NC_3") (pintype "passive+no_connect"))
    )
    (net (code "87") (name "unconnected-(U2-NC-Pad6)") (class "Default")
      (node (ref "U2") (pin "6") (pinfunction "NC_6") (pintype "passive+no_connect"))
    )
    (net (code "88") (name "unconnected-(U18-OS-Pad3)") (class "Default")
      (node (ref "U18") (pin "3") (pinfunction "OS_3") (pintype "open_collector+no_connect"))
    )
  )
)
